# 1-Schematic_TimerAndTemper.net
KiCad netlist of a schematic drawn in EasyEDA
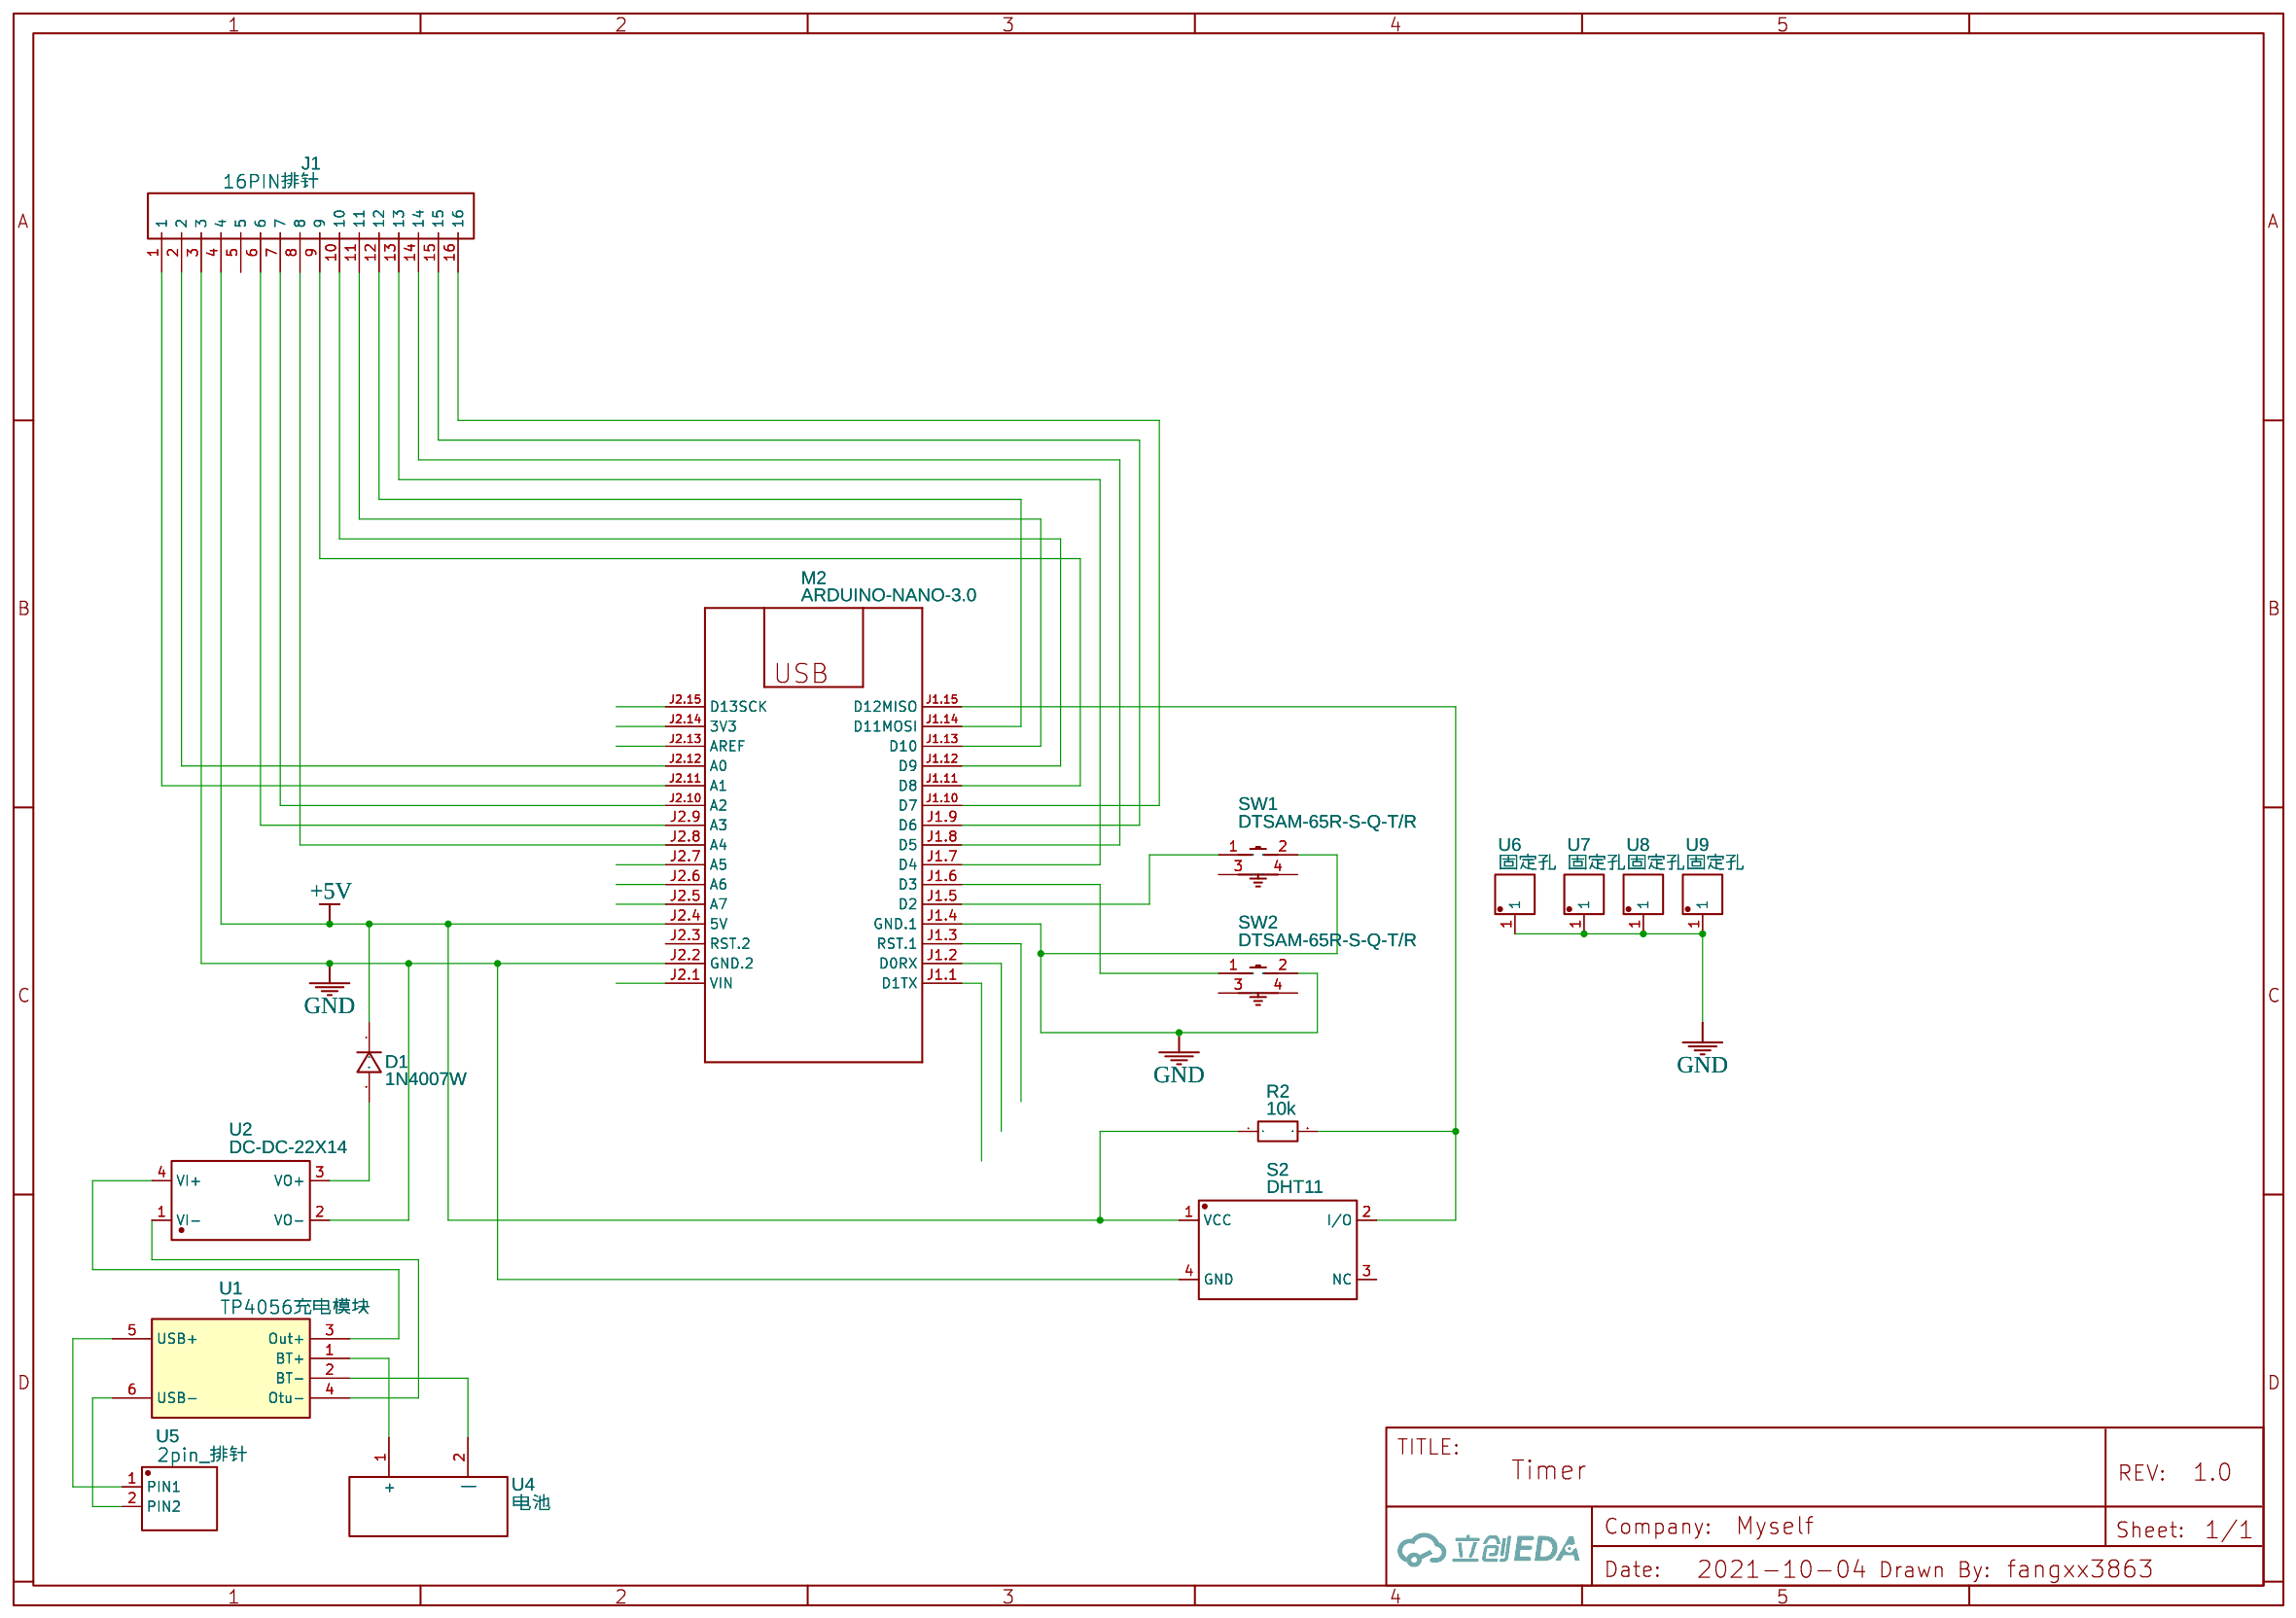
[diagram p0: schematic sheet]

(export (version "E")
  (design (tool "Eeschema 10.0.6"))
  (components
    (comp (ref "D1")
      (value "1N4007W")
      (fields (field (name "BOM_Supplier Part") "C328592"))
      (libsource (lib "") (part "1N4007W"))
    )
    (comp (ref "J1") (value "16PIN排针") (libsource (lib "") (part "16PIN排针")))
    (comp (ref "M2") (value "ARDUINO-NANO-3.0") (libsource (lib "") (part "ARDUINO-NANO-3.0")))
    (comp (ref "R2") (value "10k") (libsource (lib "") (part "R_0603_EU")))
    (comp (ref "S2")
      (value "DHT11")
      (fields (field (name "BOM_Supplier Part") "C87032"))
      (libsource (lib "") (part "DHT11"))
    )
    (comp (ref "SW1")
      (value "DTSAM-65R-S-Q-T/R")
      (fields (field (name "BOM_Supplier Part") "C501547"))
      (libsource (lib "") (part "DTSAM-65R-S-Q-T/R"))
    )
    (comp (ref "SW2")
      (value "DTSAM-65R-S-Q-T/R")
      (fields (field (name "BOM_Supplier Part") "C501547"))
      (libsource (lib "") (part "DTSAM-65R-S-Q-T/R"))
    )
    (comp (ref "U1") (value "TP4056充电模块") (libsource (lib "") (part "TP4056充电模块")))
    (comp (ref "U2") (value "DC-DC-22X14") (libsource (lib "") (part "DC-DC-22X14")))
    (comp (ref "U4") (value "电池") (libsource (lib "") (part "电池")))
    (comp (ref "U5")
      (value "2pin_排针")
      (fields (field (name "BOM_Manufacturer Part") "2pin 排针"))
      (libsource (lib "") (part "2pin_排针"))
    )
    (comp (ref "U6") (value "固定孔") (libsource (lib "") (part "固定孔")))
    (comp (ref "U7") (value "固定孔") (libsource (lib "") (part "固定孔")))
    (comp (ref "U8") (value "固定孔") (libsource (lib "") (part "固定孔")))
    (comp (ref "U9") (value "固定孔") (libsource (lib "") (part "固定孔")))
  )
  (nets
    (net (code "1") (name "+5V") (class "Default")
      (node (ref "D1") (pin "1") (pinfunction "1_1") (pintype "unspecified"))
      (node (ref "J1") (pin "4") (pinfunction "4_4") (pintype "unspecified"))
      (node (ref "M2") (pin "J2.4") (pinfunction "5V_J2.4") (pintype "passive"))
      (node (ref "R2") (pin "1") (pinfunction "1_1") (pintype "unspecified"))
      (node (ref "S2") (pin "1") (pinfunction "VCC_1") (pintype "unspecified"))
    )
    (net (code "2") (name "GND") (class "Default")
      (node (ref "J1") (pin "3") (pinfunction "3_3") (pintype "unspecified"))
      (node (ref "M2") (pin "J1.4") (pinfunction "GND.1_J1.4") (pintype "passive"))
      (node (ref "M2") (pin "J2.2") (pinfunction "GND.2_J2.2") (pintype "passive"))
      (node (ref "S2") (pin "4") (pinfunction "GND_4") (pintype "unspecified"))
      (node (ref "SW1") (pin "2") (pinfunction "2_2") (pintype "unspecified"))
      (node (ref "SW2") (pin "2") (pinfunction "2_2") (pintype "unspecified"))
      (node (ref "U2") (pin "2") (pinfunction "VO-_2") (pintype "unspecified"))
      (node (ref "U6") (pin "1") (pinfunction "1_1") (pintype "unspecified"))
      (node (ref "U7") (pin "1") (pinfunction "1_1") (pintype "unspecified"))
      (node (ref "U8") (pin "1") (pinfunction "1_1") (pintype "unspecified"))
      (node (ref "U9") (pin "1") (pinfunction "1_1") (pintype "unspecified"))
    )
    (net (code "3") (name "Net-(M2-A0)") (class "Default")
      (node (ref "J1") (pin "2") (pinfunction "2_2") (pintype "unspecified"))
      (node (ref "M2") (pin "J2.12") (pinfunction "A0_J2.12") (pintype "unspecified"))
    )
    (net (code "4") (name "Net-(M2-A1)") (class "Default")
      (node (ref "J1") (pin "1") (pinfunction "1_1") (pintype "unspecified"))
      (node (ref "M2") (pin "J2.11") (pinfunction "A1_J2.11") (pintype "unspecified"))
    )
    (net (code "5") (name "Net-(M2-A2)") (class "Default")
      (node (ref "J1") (pin "7") (pinfunction "7_7") (pintype "unspecified"))
      (node (ref "M2") (pin "J2.10") (pinfunction "A2_J2.10") (pintype "unspecified"))
    )
    (net (code "6") (name "Net-(M2-A3)") (class "Default")
      (node (ref "J1") (pin "6") (pinfunction "6_6") (pintype "unspecified"))
      (node (ref "M2") (pin "J2.9") (pinfunction "A3_J2.9") (pintype "unspecified"))
    )
    (net (code "7") (name "Net-(M2-A4)") (class "Default")
      (node (ref "J1") (pin "8") (pinfunction "8_8") (pintype "unspecified"))
      (node (ref "M2") (pin "J2.8") (pinfunction "A4_J2.8") (pintype "unspecified"))
    )
    (net (code "8") (name "Net-(M2-D2)") (class "Default")
      (node (ref "M2") (pin "J1.5") (pinfunction "D2_J1.5") (pintype "unspecified"))
      (node (ref "SW1") (pin "1") (pinfunction "1_1") (pintype "unspecified"))
    )
    (net (code "9") (name "Net-(M2-D3)") (class "Default")
      (node (ref "M2") (pin "J1.6") (pinfunction "D3_J1.6") (pintype "unspecified"))
      (node (ref "SW2") (pin "1") (pinfunction "1_1") (pintype "unspecified"))
    )
    (net (code "10") (name "Net-(M2-D4)") (class "Default")
      (node (ref "J1") (pin "13") (pinfunction "13_13") (pintype "unspecified"))
      (node (ref "M2") (pin "J1.7") (pinfunction "D4_J1.7") (pintype "unspecified"))
    )
    (net (code "11") (name "Net-(M2-D5)") (class "Default")
      (node (ref "J1") (pin "14") (pinfunction "14_14") (pintype "unspecified"))
      (node (ref "M2") (pin "J1.8") (pinfunction "D5_J1.8") (pintype "unspecified"))
    )
    (net (code "12") (name "Net-(M2-D6)") (class "Default")
      (node (ref "J1") (pin "15") (pinfunction "15_15") (pintype "unspecified"))
      (node (ref "M2") (pin "J1.9") (pinfunction "D6_J1.9") (pintype "unspecified"))
    )
    (net (code "13") (name "Net-(M2-D7)") (class "Default")
      (node (ref "J1") (pin "16") (pinfunction "16_16") (pintype "unspecified"))
      (node (ref "M2") (pin "J1.10") (pinfunction "D7_J1.10") (pintype "unspecified"))
    )
    (net (code "14") (name "Net-(M2-D8)") (class "Default")
      (node (ref "J1") (pin "9") (pinfunction "9_9") (pintype "unspecified"))
      (node (ref "M2") (pin "J1.11") (pinfunction "D8_J1.11") (pintype "unspecified"))
    )
    (net (code "15") (name "Net-(M2-D9)") (class "Default")
      (node (ref "J1") (pin "10") (pinfunction "10_10") (pintype "unspecified"))
      (node (ref "M2") (pin "J1.12") (pinfunction "D9_J1.12") (pintype "unspecified"))
    )
    (net (code "16") (name "Net-(M2-D10)") (class "Default")
      (node (ref "J1") (pin "11") (pinfunction "11_11") (pintype "unspecified"))
      (node (ref "M2") (pin "J1.13") (pinfunction "D10_J1.13") (pintype "unspecified"))
    )
    (net (code "17") (name "Net-(M2-D11MOSI)") (class "Default")
      (node (ref "J1") (pin "12") (pinfunction "12_12") (pintype "unspecified"))
      (node (ref "M2") (pin "J1.14") (pinfunction "D11MOSI_J1.14") (pintype "unspecified"))
    )
    (net (code "18") (name "Net-(M2-D12MISO)") (class "Default")
      (node (ref "M2") (pin "J1.15") (pinfunction "D12MISO_J1.15") (pintype "unspecified"))
      (node (ref "R2") (pin "2") (pinfunction "2_2") (pintype "unspecified"))
      (node (ref "S2") (pin "2") (pinfunction "I/O_2") (pintype "unspecified"))
    )
    (net (code "19") (name "Net-(U1-BT+)") (class "Default")
      (node (ref "U1") (pin "1") (pinfunction "BT+_1") (pintype "unspecified"))
      (node (ref "U4") (pin "1") (pinfunction "+_1") (pintype "unspecified"))
    )
    (net (code "20") (name "Net-(U1-BT-)") (class "Default")
      (node (ref "U1") (pin "2") (pinfunction "BT-_2") (pintype "unspecified"))
      (node (ref "U4") (pin "2") (pinfunction "|_2") (pintype "unspecified"))
    )
    (net (code "21") (name "Net-(U1-Otu-)") (class "Default")
      (node (ref "U1") (pin "4") (pinfunction "Otu-_4") (pintype "unspecified"))
      (node (ref "U2") (pin "1") (pinfunction "VI-_1") (pintype "unspecified"))
    )
    (net (code "22") (name "Net-(U1-Out+)") (class "Default")
      (node (ref "U1") (pin "3") (pinfunction "Out+_3") (pintype "unspecified"))
      (node (ref "U2") (pin "4") (pinfunction "VI+_4") (pintype "unspecified"))
    )
    (net (code "23") (name "Net-(U1-USB+)") (class "Default")
      (node (ref "U1") (pin "5") (pinfunction "USB+_5") (pintype "unspecified"))
      (node (ref "U5") (pin "1") (pinfunction "PIN1_1") (pintype "unspecified"))
    )
    (net (code "24") (name "Net-(U1-USB-)") (class "Default")
      (node (ref "U1") (pin "6") (pinfunction "USB-_6") (pintype "unspecified"))
      (node (ref "U5") (pin "2") (pinfunction "PIN2_2") (pintype "unspecified"))
    )
    (net (code "25") (name "Net-(U2-VO+)") (class "Default")
      (node (ref "D1") (pin "2") (pinfunction "2_2") (pintype "unspecified"))
      (node (ref "U2") (pin "3") (pinfunction "VO+_3") (pintype "unspecified"))
    )
    (net (code "26") (name "unconnected-(J1-Pad5)") (class "Default")
      (node (ref "J1") (pin "5") (pinfunction "5_5") (pintype "unspecified"))
    )
    (net (code "27") (name "unconnected-(M2-3V3-PadJ2.14)") (class "Default")
      (node (ref "M2") (pin "J2.14") (pinfunction "3V3_J2.14") (pintype "passive"))
    )
    (net (code "28") (name "unconnected-(M2-A5-PadJ2.7)") (class "Default")
      (node (ref "M2") (pin "J2.7") (pinfunction "A5_J2.7") (pintype "unspecified"))
    )
    (net (code "29") (name "unconnected-(M2-A6-PadJ2.6)") (class "Default")
      (node (ref "M2") (pin "J2.6") (pinfunction "A6_J2.6") (pintype "unspecified"))
    )
    (net (code "30") (name "unconnected-(M2-A7-PadJ2.5)") (class "Default")
      (node (ref "M2") (pin "J2.5") (pinfunction "A7_J2.5") (pintype "unspecified"))
    )
    (net (code "31") (name "unconnected-(M2-AREF-PadJ2.13)") (class "Default")
      (node (ref "M2") (pin "J2.13") (pinfunction "AREF_J2.13") (pintype "unspecified"))
    )
    (net (code "32") (name "unconnected-(M2-D0RX-PadJ1.2)") (class "Default")
      (node (ref "M2") (pin "J1.2") (pinfunction "D0RX_J1.2") (pintype "unspecified"))
    )
    (net (code "33") (name "unconnected-(M2-D1TX-PadJ1.1)") (class "Default")
      (node (ref "M2") (pin "J1.1") (pinfunction "D1TX_J1.1") (pintype "unspecified"))
    )
    (net (code "34") (name "unconnected-(M2-D13SCK-PadJ2.15)") (class "Default")
      (node (ref "M2") (pin "J2.15") (pinfunction "D13SCK_J2.15") (pintype "unspecified"))
    )
    (net (code "35") (name "unconnected-(M2-RST.1-PadJ1.3)") (class "Default")
      (node (ref "M2") (pin "J1.3") (pinfunction "RST.1_J1.3") (pintype "unspecified"))
    )
    (net (code "36") (name "unconnected-(M2-RST.2-PadJ2.3)") (class "Default")
      (node (ref "M2") (pin "J2.3") (pinfunction "RST.2_J2.3") (pintype "unspecified"))
    )
    (net (code "37") (name "unconnected-(M2-VIN-PadJ2.1)") (class "Default")
      (node (ref "M2") (pin "J2.1") (pinfunction "VIN_J2.1") (pintype "passive"))
    )
    (net (code "38") (name "unconnected-(S2-NC-Pad3)") (class "Default")
      (node (ref "S2") (pin "3") (pinfunction "NC_3") (pintype "unspecified"))
    )
    (net (code "39") (name "unconnected-(SW1-Pad3)") (class "Default")
      (node (ref "SW1") (pin "3") (pinfunction "3_3") (pintype "unspecified"))
    )
    (net (code "40") (name "unconnected-(SW1-Pad4)") (class "Default")
      (node (ref "SW1") (pin "4") (pinfunction "4_4") (pintype "unspecified"))
    )
    (net (code "41") (name "unconnected-(SW2-Pad3)") (class "Default")
      (node (ref "SW2") (pin "3") (pinfunction "3_3") (pintype "unspecified"))
    )
    (net (code "42") (name "unconnected-(SW2-Pad4)") (class "Default")
      (node (ref "SW2") (pin "4") (pinfunction "4_4") (pintype "unspecified"))
    )
  )
)
